# me433.net
KiCad netlist of a schematic drawn in EAGLE
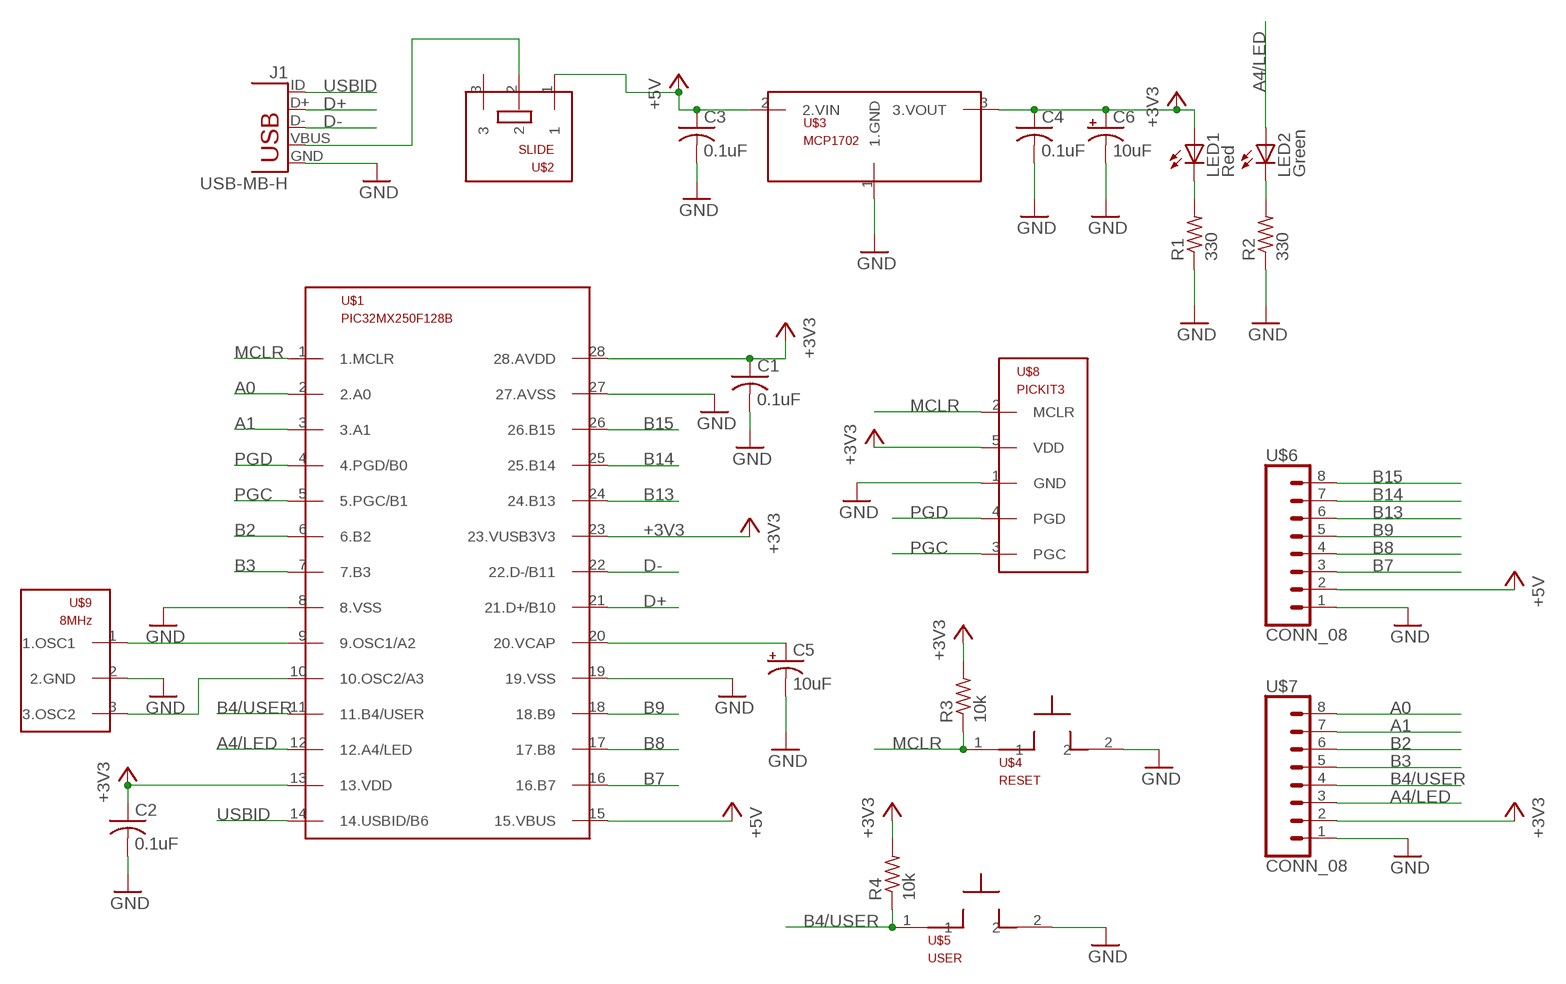
[diagram p0: schematic, sheet 1]

(export (version "E")
  (design (tool "Eeschema 10.0.6"))
  (components
    (comp (ref "C1")
      (value "0.1uF")
      (footprint "eagle-import:C025-025X050")
      (libsource (lib "eagle-import") (part "C-US025-025X050"))
    )
    (comp (ref "C2")
      (value "0.1uF")
      (footprint "eagle-import:C025-025X050")
      (libsource (lib "eagle-import") (part "C-US025-025X050"))
    )
    (comp (ref "C3")
      (value "0.1uF")
      (footprint "eagle-import:C025-025X050")
      (libsource (lib "eagle-import") (part "C-US025-025X050"))
    )
    (comp (ref "C4")
      (value "0.1uF")
      (footprint "eagle-import:C025-025X050")
      (libsource (lib "eagle-import") (part "C-US025-025X050"))
    )
    (comp (ref "C5")
      (value "10uF")
      (footprint "eagle-import:B45181B")
      (libsource (lib "eagle-import") (part "CPOL-USB45181B"))
    )
    (comp (ref "C6")
      (value "10uF")
      (footprint "eagle-import:B45181B")
      (libsource (lib "eagle-import") (part "CPOL-USB45181B"))
    )
    (comp (ref "J1")
      (value "USB-MB-H")
      (footprint "eagle-import:USB-MB-H")
      (libsource (lib "eagle-import") (part "USB-MB-H"))
    )
    (comp (ref "LED1")
      (value "Red")
      (footprint "eagle-import:LED3MM")
      (libsource (lib "eagle-import") (part "LED3MM"))
    )
    (comp (ref "LED2")
      (value "Green")
      (footprint "eagle-import:LED3MM")
      (libsource (lib "eagle-import") (part "LED3MM"))
    )
    (comp (ref "R1")
      (value "330")
      (footprint "eagle-import:0207_10")
      (libsource (lib "eagle-import") (part "R-US_0207/10"))
    )
    (comp (ref "R2")
      (value "330")
      (footprint "eagle-import:0207_10")
      (libsource (lib "eagle-import") (part "R-US_0207/10"))
    )
    (comp (ref "R3")
      (value "10k")
      (footprint "eagle-import:0207_10")
      (libsource (lib "eagle-import") (part "R-US_0207/10"))
    )
    (comp (ref "R4")
      (value "10k")
      (footprint "eagle-import:0207_10")
      (libsource (lib "eagle-import") (part "R-US_0207/10"))
    )
    (comp (ref "U$1")
      (value "PIC32MX250F128B")
      (footprint "eagle-import:DIL28-3")
      (libsource (lib "eagle-import") (part "PIC32MX250F128B"))
    )
    (comp (ref "U$2")
      (value "SLIDE")
      (footprint "eagle-import:SLIDE")
      (libsource (lib "eagle-import") (part "SLIDE"))
    )
    (comp (ref "U$3")
      (value "MCP1702")
      (footprint "eagle-import:TO92")
      (libsource (lib "eagle-import") (part "MCP1702"))
    )
    (comp (ref "U$4")
      (value "RESET")
      (footprint "eagle-import:PB")
      (libsource (lib "eagle-import") (part "PB"))
    )
    (comp (ref "U$5")
      (value "USER")
      (footprint "eagle-import:PB")
      (libsource (lib "eagle-import") (part "PB"))
    )
    (comp (ref "U$6")
      (value "CONN_08")
      (footprint "eagle-import:1X08")
      (libsource (lib "eagle-import") (part "CONN_08"))
    )
    (comp (ref "U$7")
      (value "CONN_08")
      (footprint "eagle-import:1X08")
      (libsource (lib "eagle-import") (part "CONN_08"))
    )
    (comp (ref "U$8")
      (value "PICKIT3")
      (footprint "eagle-import:1X05")
      (libsource (lib "eagle-import") (part "PICKIT3"))
    )
    (comp (ref "U$9")
      (value "8MHz")
      (footprint "eagle-import:OSC")
      (libsource (lib "eagle-import") (part "OSC"))
    )
  )
  (nets
    (net (code "1") (name "+3V3") (class "Default")
      (node (ref "C1") (pin "1") (pinfunction "1_1") (pintype "passive"))
      (node (ref "C2") (pin "1") (pinfunction "1_1") (pintype "passive"))
      (node (ref "C4") (pin "1") (pinfunction "1_1") (pintype "passive"))
      (node (ref "C6") (pin "+") (pinfunction "+_+") (pintype "passive"))
      (node (ref "LED1") (pin "A") (pinfunction "A_A") (pintype "passive"))
      (node (ref "R3") (pin "2") (pinfunction "2_2") (pintype "passive"))
      (node (ref "R4") (pin "2") (pinfunction "2_2") (pintype "passive"))
      (node (ref "U$1") (pin "13") (pinfunction "13.VDD_13") (pintype "bidirectional"))
      (node (ref "U$1") (pin "23") (pinfunction "23.VUSB3V3_23") (pintype "bidirectional"))
      (node (ref "U$1") (pin "28") (pinfunction "28.AVDD_28") (pintype "bidirectional"))
      (node (ref "U$3") (pin "3") (pinfunction "3.VOUT_3") (pintype "bidirectional"))
      (node (ref "U$7") (pin "2") (pinfunction "2_2") (pintype "passive"))
      (node (ref "U$8") (pin "5") (pinfunction "VDD_5") (pintype "bidirectional"))
    )
    (net (code "2") (name "+5V") (class "Default")
      (node (ref "C3") (pin "1") (pinfunction "1_1") (pintype "passive"))
      (node (ref "U$1") (pin "15") (pinfunction "15.VBUS_15") (pintype "bidirectional"))
      (node (ref "U$2") (pin "1") (pinfunction "1_1") (pintype "bidirectional"))
      (node (ref "U$3") (pin "2") (pinfunction "2.VIN_2") (pintype "bidirectional"))
      (node (ref "U$6") (pin "2") (pinfunction "2_2") (pintype "passive"))
    )
    (net (code "3") (name "/A0") (class "Default")
      (node (ref "U$1") (pin "2") (pinfunction "2.A0_2") (pintype "bidirectional"))
      (node (ref "U$7") (pin "8") (pinfunction "8_8") (pintype "passive"))
    )
    (net (code "4") (name "/A1") (class "Default")
      (node (ref "U$1") (pin "3") (pinfunction "3.A1_3") (pintype "bidirectional"))
      (node (ref "U$7") (pin "7") (pinfunction "7_7") (pintype "passive"))
    )
    (net (code "5") (name "/A4{slash}LED") (class "Default")
      (node (ref "LED2") (pin "A") (pinfunction "A_A") (pintype "passive"))
      (node (ref "U$1") (pin "12") (pinfunction "12.A4/LED_12") (pintype "bidirectional"))
      (node (ref "U$7") (pin "3") (pinfunction "3_3") (pintype "passive"))
    )
    (net (code "6") (name "/B2") (class "Default")
      (node (ref "U$1") (pin "6") (pinfunction "6.B2_6") (pintype "bidirectional"))
      (node (ref "U$7") (pin "6") (pinfunction "6_6") (pintype "passive"))
    )
    (net (code "7") (name "/B3") (class "Default")
      (node (ref "U$1") (pin "7") (pinfunction "7.B3_7") (pintype "bidirectional"))
      (node (ref "U$7") (pin "5") (pinfunction "5_5") (pintype "passive"))
    )
    (net (code "8") (name "/B4{slash}USER") (class "Default")
      (node (ref "R4") (pin "1") (pinfunction "1_1") (pintype "passive"))
      (node (ref "U$1") (pin "11") (pinfunction "11.B4/USER_11") (pintype "bidirectional"))
      (node (ref "U$5") (pin "1") (pinfunction "1_1") (pintype "bidirectional"))
      (node (ref "U$7") (pin "4") (pinfunction "4_4") (pintype "passive"))
    )
    (net (code "9") (name "/B7") (class "Default")
      (node (ref "U$1") (pin "16") (pinfunction "16.B7_16") (pintype "bidirectional"))
      (node (ref "U$6") (pin "3") (pinfunction "3_3") (pintype "passive"))
    )
    (net (code "10") (name "/B8") (class "Default")
      (node (ref "U$1") (pin "17") (pinfunction "17.B8_17") (pintype "bidirectional"))
      (node (ref "U$6") (pin "4") (pinfunction "4_4") (pintype "passive"))
    )
    (net (code "11") (name "/B9") (class "Default")
      (node (ref "U$1") (pin "18") (pinfunction "18.B9_18") (pintype "bidirectional"))
      (node (ref "U$6") (pin "5") (pinfunction "5_5") (pintype "passive"))
    )
    (net (code "12") (name "/B13") (class "Default")
      (node (ref "U$1") (pin "24") (pinfunction "24.B13_24") (pintype "bidirectional"))
      (node (ref "U$6") (pin "6") (pinfunction "6_6") (pintype "passive"))
    )
    (net (code "13") (name "/B14") (class "Default")
      (node (ref "U$1") (pin "25") (pinfunction "25.B14_25") (pintype "bidirectional"))
      (node (ref "U$6") (pin "7") (pinfunction "7_7") (pintype "passive"))
    )
    (net (code "14") (name "/B15") (class "Default")
      (node (ref "U$1") (pin "26") (pinfunction "26.B15_26") (pintype "bidirectional"))
      (node (ref "U$6") (pin "8") (pinfunction "8_8") (pintype "passive"))
    )
    (net (code "15") (name "/D+") (class "Default")
      (node (ref "J1") (pin "D+") (pinfunction "D+_D+") (pintype "bidirectional"))
      (node (ref "U$1") (pin "21") (pinfunction "21.D+/B10_21") (pintype "bidirectional"))
    )
    (net (code "16") (name "/D-") (class "Default")
      (node (ref "J1") (pin "D-") (pinfunction "D-_D-") (pintype "bidirectional"))
      (node (ref "U$1") (pin "22") (pinfunction "22.D-/B11_22") (pintype "bidirectional"))
    )
    (net (code "17") (name "/MCLR") (class "Default")
      (node (ref "R3") (pin "1") (pinfunction "1_1") (pintype "passive"))
      (node (ref "U$1") (pin "1") (pinfunction "1.MCLR_1") (pintype "bidirectional"))
      (node (ref "U$4") (pin "1") (pinfunction "1_1") (pintype "bidirectional"))
      (node (ref "U$8") (pin "2") (pinfunction "MCLR_2") (pintype "bidirectional"))
    )
    (net (code "18") (name "/PGC") (class "Default")
      (node (ref "U$1") (pin "5") (pinfunction "5.PGC/B1_5") (pintype "bidirectional"))
      (node (ref "U$8") (pin "3") (pinfunction "PGC_3") (pintype "bidirectional"))
    )
    (net (code "19") (name "/PGD") (class "Default")
      (node (ref "U$1") (pin "4") (pinfunction "4.PGD/B0_4") (pintype "bidirectional"))
      (node (ref "U$8") (pin "4") (pinfunction "PGD_4") (pintype "bidirectional"))
    )
    (net (code "20") (name "/USBID") (class "Default")
      (node (ref "J1") (pin "ID") (pinfunction "ID_ID") (pintype "bidirectional"))
      (node (ref "U$1") (pin "14") (pinfunction "14.USBID/B6_14") (pintype "bidirectional"))
    )
    (net (code "21") (name "GND") (class "Default")
      (node (ref "C1") (pin "2") (pinfunction "2_2") (pintype "passive"))
      (node (ref "C2") (pin "2") (pinfunction "2_2") (pintype "passive"))
      (node (ref "C3") (pin "2") (pinfunction "2_2") (pintype "passive"))
      (node (ref "C4") (pin "2") (pinfunction "2_2") (pintype "passive"))
      (node (ref "C5") (pin "-") (pinfunction "-_-") (pintype "passive"))
      (node (ref "C6") (pin "-") (pinfunction "-_-") (pintype "passive"))
      (node (ref "J1") (pin "GND") (pinfunction "GND_GND") (pintype "bidirectional"))
      (node (ref "R1") (pin "1") (pinfunction "1_1") (pintype "passive"))
      (node (ref "R2") (pin "1") (pinfunction "1_1") (pintype "passive"))
      (node (ref "U$1") (pin "19") (pinfunction "19.VSS_19") (pintype "bidirectional"))
      (node (ref "U$1") (pin "27") (pinfunction "27.AVSS_27") (pintype "bidirectional"))
      (node (ref "U$1") (pin "8") (pinfunction "8.VSS_8") (pintype "bidirectional"))
      (node (ref "U$3") (pin "1") (pinfunction "1.GND_1") (pintype "bidirectional"))
      (node (ref "U$4") (pin "2") (pinfunction "2_2") (pintype "bidirectional"))
      (node (ref "U$5") (pin "2") (pinfunction "2_2") (pintype "bidirectional"))
      (node (ref "U$6") (pin "1") (pinfunction "1_1") (pintype "passive"))
      (node (ref "U$7") (pin "1") (pinfunction "1_1") (pintype "passive"))
      (node (ref "U$8") (pin "1") (pinfunction "GND_1") (pintype "bidirectional"))
      (node (ref "U$9") (pin "2") (pinfunction "2.GND_2") (pintype "bidirectional"))
    )
    (net (code "22") (name "Net-(J1-PadVBUS)") (class "Default")
      (node (ref "J1") (pin "VBUS") (pinfunction "VBUS_VBUS") (pintype "bidirectional"))
      (node (ref "U$2") (pin "2") (pinfunction "2_2") (pintype "bidirectional"))
    )
    (net (code "23") (name "Net-(LED1-C)") (class "Default")
      (node (ref "LED1") (pin "K") (pinfunction "C_K") (pintype "passive"))
      (node (ref "R1") (pin "2") (pinfunction "2_2") (pintype "passive"))
    )
    (net (code "24") (name "Net-(LED2-C)") (class "Default")
      (node (ref "LED2") (pin "K") (pinfunction "C_K") (pintype "passive"))
      (node (ref "R2") (pin "2") (pinfunction "2_2") (pintype "passive"))
    )
    (net (code "25") (name "Net-(U$1-9.OSC1{slash}A2)") (class "Default")
      (node (ref "U$1") (pin "9") (pinfunction "9.OSC1/A2_9") (pintype "bidirectional"))
      (node (ref "U$9") (pin "1") (pinfunction "1.OSC1_1") (pintype "bidirectional"))
    )
    (net (code "26") (name "Net-(U$1-10.OSC2{slash}A3)") (class "Default")
      (node (ref "U$1") (pin "10") (pinfunction "10.OSC2/A3_10") (pintype "bidirectional"))
      (node (ref "U$9") (pin "3") (pinfunction "3.OSC2_3") (pintype "bidirectional"))
    )
    (net (code "27") (name "Net-(U$1-20.VCAP)") (class "Default")
      (node (ref "C5") (pin "+") (pinfunction "+_+") (pintype "passive"))
      (node (ref "U$1") (pin "20") (pinfunction "20.VCAP_20") (pintype "bidirectional"))
    )
    (net (code "28") (name "unconnected-(U$2-Pad3)") (class "Default")
      (node (ref "U$2") (pin "3") (pinfunction "3_3") (pintype "bidirectional"))
    )
  )
)
